# Shruthi-Analog-SVF-v02.net
KiCad netlist of a schematic drawn in EAGLE
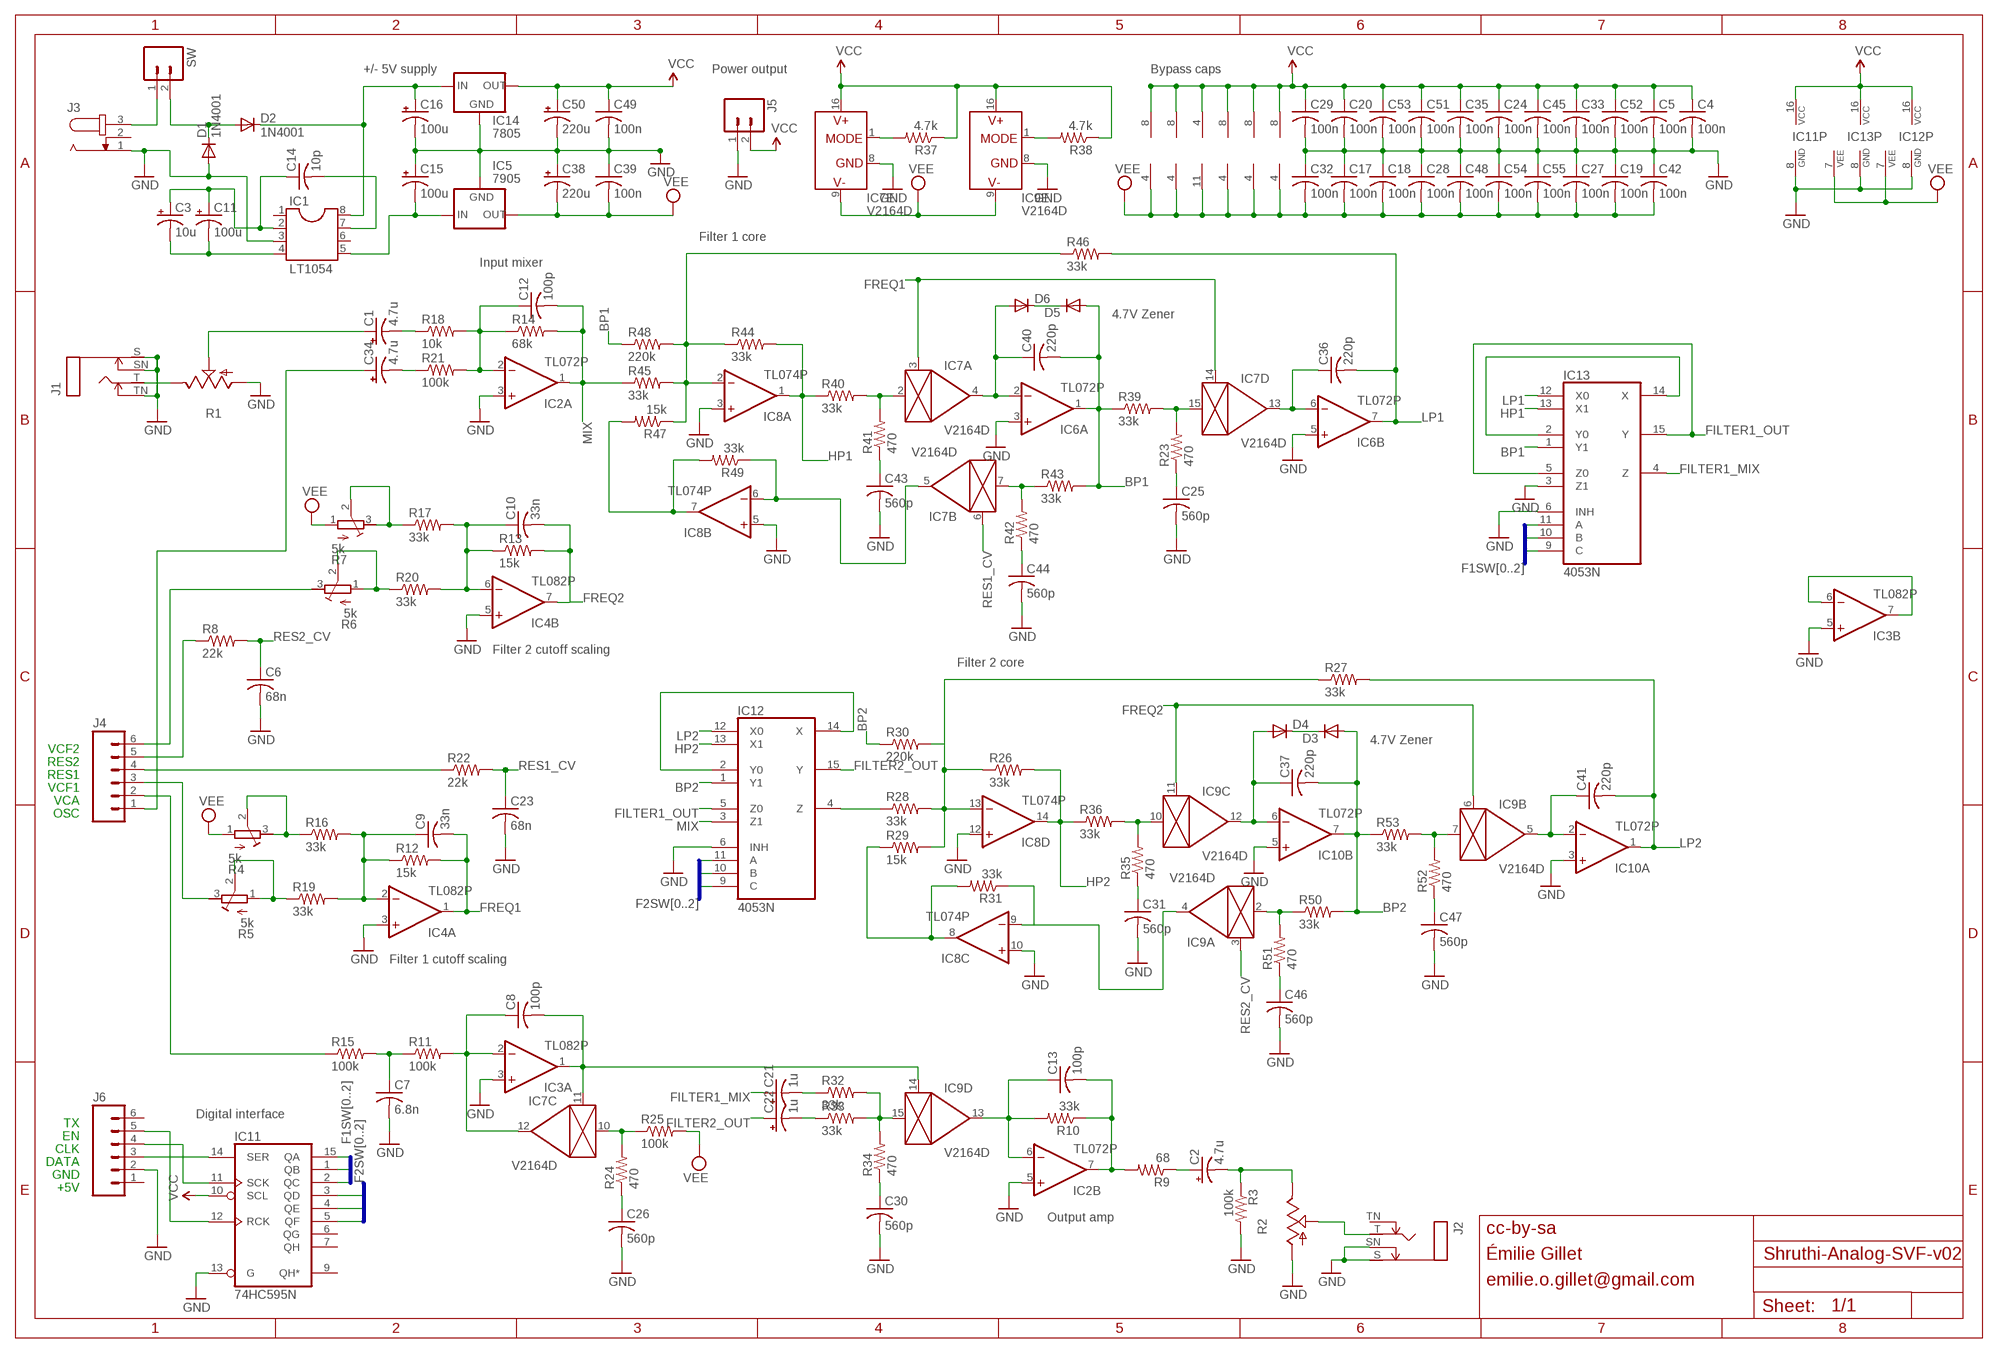
[diagram p0: schematic, sheet 1]

(export (version "E")
  (design (tool "Eeschema 10.0.6"))
  (components
    (comp (ref "C1")
      (value "4.7u")
      (footprint "eagle-import:E2,5-6")
      (libsource (lib "eagle-import") (part "CPOL-USE2.5-6"))
    )
    (comp (ref "C2")
      (value "4.7u")
      (footprint "eagle-import:E2,5-6")
      (libsource (lib "eagle-import") (part "CPOL-USE2.5-6"))
    )
    (comp (ref "C3")
      (value "10u")
      (footprint "eagle-import:E2,5-5")
      (libsource (lib "eagle-import") (part "CPOL-USE2.5-5"))
    )
    (comp (ref "C4")
      (value "100n")
      (footprint "eagle-import:C025-025X050")
      (libsource (lib "eagle-import") (part "C-US025-025X050"))
    )
    (comp (ref "C5")
      (value "100n")
      (footprint "eagle-import:C025-025X050")
      (libsource (lib "eagle-import") (part "C-US025-025X050"))
    )
    (comp (ref "C6")
      (value "68n")
      (footprint "eagle-import:C050-025X075")
      (libsource (lib "eagle-import") (part "C-US050-025X075"))
    )
    (comp (ref "C7")
      (value "6.8n")
      (footprint "eagle-import:C025-025X050")
      (libsource (lib "eagle-import") (part "C-US025-025X050"))
    )
    (comp (ref "C8")
      (value "100p")
      (footprint "eagle-import:C025-025X050")
      (libsource (lib "eagle-import") (part "C-US025-025X050"))
    )
    (comp (ref "C9")
      (value "33n")
      (footprint "eagle-import:C050-025X075")
      (libsource (lib "eagle-import") (part "C-US050-025X075"))
    )
    (comp (ref "C10")
      (value "33n")
      (footprint "eagle-import:C050-025X075")
      (libsource (lib "eagle-import") (part "C-US050-025X075"))
    )
    (comp (ref "C11")
      (value "100u")
      (footprint "eagle-import:E2,5-6")
      (libsource (lib "eagle-import") (part "CPOL-USE2.5-6"))
    )
    (comp (ref "C12")
      (value "100p")
      (footprint "eagle-import:C025-025X050")
      (libsource (lib "eagle-import") (part "C-US025-025X050"))
    )
    (comp (ref "C13")
      (value "100p")
      (footprint "eagle-import:C025-025X050")
      (libsource (lib "eagle-import") (part "C-US025-025X050"))
    )
    (comp (ref "C14")
      (value "10p")
      (footprint "eagle-import:C025-025X050")
      (libsource (lib "eagle-import") (part "C-US025-025X050"))
    )
    (comp (ref "C15")
      (value "100u")
      (footprint "eagle-import:E2,5-7")
      (libsource (lib "eagle-import") (part "CPOL-USE2.5-7"))
    )
    (comp (ref "C16")
      (value "100u")
      (footprint "eagle-import:E2,5-7")
      (libsource (lib "eagle-import") (part "CPOL-USE2.5-7"))
    )
    (comp (ref "C17")
      (value "100n")
      (footprint "eagle-import:C025-025X050")
      (libsource (lib "eagle-import") (part "C-US025-025X050"))
    )
    (comp (ref "C18")
      (value "100n")
      (footprint "eagle-import:C025-025X050")
      (libsource (lib "eagle-import") (part "C-US025-025X050"))
    )
    (comp (ref "C19")
      (value "100n")
      (footprint "eagle-import:C025-025X050")
      (libsource (lib "eagle-import") (part "C-US025-025X050"))
    )
    (comp (ref "C20")
      (value "100n")
      (footprint "eagle-import:C025-025X050")
      (libsource (lib "eagle-import") (part "C-US025-025X050"))
    )
    (comp (ref "C21")
      (value "1u")
      (footprint "eagle-import:E2,5-5")
      (libsource (lib "eagle-import") (part "CPOL-USE2.5-5"))
    )
    (comp (ref "C22")
      (value "1u")
      (footprint "eagle-import:E2,5-5")
      (libsource (lib "eagle-import") (part "CPOL-USE2.5-5"))
    )
    (comp (ref "C23")
      (value "68n")
      (footprint "eagle-import:C050-025X075")
      (libsource (lib "eagle-import") (part "C-US050-025X075"))
    )
    (comp (ref "C24")
      (value "100n")
      (footprint "eagle-import:C025-025X050")
      (libsource (lib "eagle-import") (part "C-US025-025X050"))
    )
    (comp (ref "C25")
      (value "560p")
      (footprint "eagle-import:C025-025X050")
      (libsource (lib "eagle-import") (part "C-US025-025X050"))
    )
    (comp (ref "C26")
      (value "560p")
      (footprint "eagle-import:C025-025X050")
      (libsource (lib "eagle-import") (part "C-US025-025X050"))
    )
    (comp (ref "C27")
      (value "100n")
      (footprint "eagle-import:C025-025X050")
      (libsource (lib "eagle-import") (part "C-US025-025X050"))
    )
    (comp (ref "C28")
      (value "100n")
      (footprint "eagle-import:C025-025X050")
      (libsource (lib "eagle-import") (part "C-US025-025X050"))
    )
    (comp (ref "C29")
      (value "100n")
      (footprint "eagle-import:C025-025X050")
      (libsource (lib "eagle-import") (part "C-US025-025X050"))
    )
    (comp (ref "C30")
      (value "560p")
      (footprint "eagle-import:C025-025X050")
      (libsource (lib "eagle-import") (part "C-US025-025X050"))
    )
    (comp (ref "C31")
      (value "560p")
      (footprint "eagle-import:C025-025X050")
      (libsource (lib "eagle-import") (part "C-US025-025X050"))
    )
    (comp (ref "C32")
      (value "100n")
      (footprint "eagle-import:C025-025X050")
      (libsource (lib "eagle-import") (part "C-US025-025X050"))
    )
    (comp (ref "C33")
      (value "100n")
      (footprint "eagle-import:C025-025X050")
      (libsource (lib "eagle-import") (part "C-US025-025X050"))
    )
    (comp (ref "C34")
      (value "4.7u")
      (footprint "eagle-import:E2,5-6")
      (libsource (lib "eagle-import") (part "CPOL-USE2.5-6"))
    )
    (comp (ref "C35")
      (value "100n")
      (footprint "eagle-import:C025-025X050")
      (libsource (lib "eagle-import") (part "C-US025-025X050"))
    )
    (comp (ref "C36")
      (value "220p")
      (footprint "eagle-import:C025-025X050")
      (libsource (lib "eagle-import") (part "C-US025-025X050"))
    )
    (comp (ref "C37")
      (value "220p")
      (footprint "eagle-import:C025-025X050")
      (libsource (lib "eagle-import") (part "C-US025-025X050"))
    )
    (comp (ref "C38")
      (value "220u")
      (footprint "eagle-import:E5-10,5")
      (libsource (lib "eagle-import") (part "CPOL-USE5-10.5"))
    )
    (comp (ref "C39")
      (value "100n")
      (footprint "eagle-import:C025-025X050")
      (libsource (lib "eagle-import") (part "C-US025-025X050"))
    )
    (comp (ref "C40")
      (value "220p")
      (footprint "eagle-import:C025-025X050")
      (libsource (lib "eagle-import") (part "C-US025-025X050"))
    )
    (comp (ref "C41")
      (value "220p")
      (footprint "eagle-import:C025-025X050")
      (libsource (lib "eagle-import") (part "C-US025-025X050"))
    )
    (comp (ref "C42")
      (value "100n")
      (footprint "eagle-import:C025-025X050")
      (libsource (lib "eagle-import") (part "C-US025-025X050"))
    )
    (comp (ref "C43")
      (value "560p")
      (footprint "eagle-import:C025-025X050")
      (libsource (lib "eagle-import") (part "C-US025-025X050"))
    )
    (comp (ref "C44")
      (value "560p")
      (footprint "eagle-import:C025-025X050")
      (libsource (lib "eagle-import") (part "C-US025-025X050"))
    )
    (comp (ref "C45")
      (value "100n")
      (footprint "eagle-import:C025-025X050")
      (libsource (lib "eagle-import") (part "C-US025-025X050"))
    )
    (comp (ref "C46")
      (value "560p")
      (footprint "eagle-import:C025-025X050")
      (libsource (lib "eagle-import") (part "C-US025-025X050"))
    )
    (comp (ref "C47")
      (value "560p")
      (footprint "eagle-import:C025-025X050")
      (libsource (lib "eagle-import") (part "C-US025-025X050"))
    )
    (comp (ref "C48")
      (value "100n")
      (footprint "eagle-import:C025-025X050")
      (libsource (lib "eagle-import") (part "C-US025-025X050"))
    )
    (comp (ref "C49")
      (value "100n")
      (footprint "eagle-import:C025-025X050")
      (libsource (lib "eagle-import") (part "C-US025-025X050"))
    )
    (comp (ref "C50")
      (value "220u")
      (footprint "eagle-import:E5-10,5")
      (libsource (lib "eagle-import") (part "CPOL-USE5-10.5"))
    )
    (comp (ref "C51")
      (value "100n")
      (footprint "eagle-import:C025-025X050")
      (libsource (lib "eagle-import") (part "C-US025-025X050"))
    )
    (comp (ref "C52")
      (value "100n")
      (footprint "eagle-import:C025-025X050")
      (libsource (lib "eagle-import") (part "C-US025-025X050"))
    )
    (comp (ref "C53")
      (value "100n")
      (footprint "eagle-import:C025-025X050")
      (libsource (lib "eagle-import") (part "C-US025-025X050"))
    )
    (comp (ref "C54")
      (value "100n")
      (footprint "eagle-import:C025-025X050")
      (libsource (lib "eagle-import") (part "C-US025-025X050"))
    )
    (comp (ref "C55")
      (value "100n")
      (footprint "eagle-import:C025-025X050")
      (libsource (lib "eagle-import") (part "C-US025-025X050"))
    )
    (comp (ref "D1")
      (value "1N4001")
      (footprint "eagle-import:DO41-10")
      (libsource (lib "eagle-import") (part "1N4004"))
    )
    (comp (ref "D2")
      (value "1N4001")
      (footprint "eagle-import:DO41-10")
      (libsource (lib "eagle-import") (part "1N4004"))
    )
    (comp (ref "D3")
      (value "DIODE-D-5")
      (footprint "eagle-import:D-5")
      (libsource (lib "eagle-import") (part "DIODE-D-5"))
    )
    (comp (ref "D4")
      (value "DIODE-D-5")
      (footprint "eagle-import:D-5")
      (libsource (lib "eagle-import") (part "DIODE-D-5"))
    )
    (comp (ref "D5")
      (value "DIODE-D-5")
      (footprint "eagle-import:D-5")
      (libsource (lib "eagle-import") (part "DIODE-D-5"))
    )
    (comp (ref "D6")
      (value "DIODE-D-5")
      (footprint "eagle-import:D-5")
      (libsource (lib "eagle-import") (part "DIODE-D-5"))
    )
    (comp (ref "IC1")
      (value "LT1054")
      (footprint "eagle-import:DIL08")
      (libsource (lib "eagle-import") (part "DIL8"))
    )
    (comp (ref "IC2")
      (value "TL072P")
      (footprint "eagle-import:DIL08")
      (libsource (lib "eagle-import") (part "TL072P"))
    )
    (comp (ref "IC3")
      (value "TL082P")
      (footprint "eagle-import:DIL08")
      (libsource (lib "eagle-import") (part "TL072P"))
    )
    (comp (ref "IC4")
      (value "TL082P")
      (footprint "eagle-import:DIL08")
      (libsource (lib "eagle-import") (part "TL072P"))
    )
    (comp (ref "IC5")
      (value "7905")
      (footprint "eagle-import:79XXS")
      (libsource (lib "eagle-import") (part "79XXS"))
    )
    (comp (ref "IC6")
      (value "TL072P")
      (footprint "eagle-import:DIL08")
      (libsource (lib "eagle-import") (part "TL072P"))
    )
    (comp (ref "IC7")
      (value "V2164D")
      (footprint "eagle-import:DIL16")
      (libsource (lib "eagle-import") (part "SSM2164P"))
    )
    (comp (ref "IC8")
      (value "TL074P")
      (footprint "eagle-import:DIL14")
      (libsource (lib "eagle-import") (part "TL074P"))
    )
    (comp (ref "IC9")
      (value "V2164D")
      (footprint "eagle-import:DIL16")
      (libsource (lib "eagle-import") (part "SSM2164P"))
    )
    (comp (ref "IC10")
      (value "TL072P")
      (footprint "eagle-import:DIL08")
      (libsource (lib "eagle-import") (part "TL072P"))
    )
    (comp (ref "IC11")
      (value "74HC595N")
      (footprint "eagle-import:DIL16")
      (libsource (lib "eagle-import") (part "74595NHC"))
    )
    (comp (ref "IC12")
      (value "4053N")
      (footprint "eagle-import:DIL16")
      (libsource (lib "eagle-import") (part "4053N"))
    )
    (comp (ref "IC13")
      (value "4053N")
      (footprint "eagle-import:DIL16")
      (libsource (lib "eagle-import") (part "4053N"))
    )
    (comp (ref "IC14")
      (value "7805")
      (footprint "eagle-import:78XXS")
      (libsource (lib "eagle-import") (part "78XXS"))
    )
    (comp (ref "J1")
      (value "MONOSWS")
      (footprint "eagle-import:NMJ4HC-S")
      (libsource (lib "eagle-import") (part "MONOSWS"))
    )
    (comp (ref "J2")
      (value "MONOSWS")
      (footprint "eagle-import:NMJ4HC-S")
      (libsource (lib "eagle-import") (part "MONOSWS"))
    )
    (comp (ref "J3")
      (value "JACK-PLUG1")
      (footprint "eagle-import:SPC4078")
      (libsource (lib "eagle-import") (part "JACK-PLUG1"))
    )
    (comp (ref "J4")
      (value "M06SIP")
      (footprint "eagle-import:1X06")
      (libsource (lib "eagle-import") (part "M06SIP"))
    )
    (comp (ref "J5")
      (value "M02PTH")
      (footprint "eagle-import:1X02")
      (libsource (lib "eagle-import") (part "M02PTH"))
    )
    (comp (ref "J6")
      (value "M06SIP")
      (footprint "eagle-import:1X06")
      (libsource (lib "eagle-import") (part "M06SIP"))
    )
    (comp (ref "R1")
      (value "POT_USCABLED")
      (footprint "eagle-import:CABLE_POT_6MM")
      (libsource (lib "eagle-import") (part "POT_USCABLED"))
    )
    (comp (ref "R2")
      (value "POT_USCABLED")
      (footprint "eagle-import:CABLE_POT_6MM")
      (libsource (lib "eagle-import") (part "POT_USCABLED"))
    )
    (comp (ref "R3")
      (value "100k")
      (footprint "eagle-import:0204_7")
      (libsource (lib "eagle-import") (part "R-US_0204/7"))
    )
    (comp (ref "R4")
      (value "5k")
      (footprint "eagle-import:RTRIM3296W")
      (libsource (lib "eagle-import") (part "R-TRIMM3296W"))
    )
    (comp (ref "R5")
      (value "5k")
      (footprint "eagle-import:RTRIM3296W")
      (libsource (lib "eagle-import") (part "R-TRIMM3296W"))
    )
    (comp (ref "R6")
      (value "5k")
      (footprint "eagle-import:RTRIM3296W")
      (libsource (lib "eagle-import") (part "R-TRIMM3296W"))
    )
    (comp (ref "R7")
      (value "5k")
      (footprint "eagle-import:RTRIM3296W")
      (libsource (lib "eagle-import") (part "R-TRIMM3296W"))
    )
    (comp (ref "R8")
      (value "22k")
      (footprint "eagle-import:0204_7")
      (libsource (lib "eagle-import") (part "R-US_0204/7"))
    )
    (comp (ref "R9")
      (value "68")
      (footprint "eagle-import:0204_7")
      (libsource (lib "eagle-import") (part "R-US_0204/7"))
    )
    (comp (ref "R10")
      (value "33k")
      (footprint "eagle-import:0204_7")
      (libsource (lib "eagle-import") (part "R-US_0204/7"))
    )
    (comp (ref "R11")
      (value "100k")
      (footprint "eagle-import:0204_7")
      (libsource (lib "eagle-import") (part "R-US_0204/7"))
    )
    (comp (ref "R12")
      (value "15k")
      (footprint "eagle-import:0204_7")
      (libsource (lib "eagle-import") (part "R-US_0204/7"))
    )
    (comp (ref "R13")
      (value "15k")
      (footprint "eagle-import:0204_7")
      (libsource (lib "eagle-import") (part "R-US_0204/7"))
    )
    (comp (ref "R14")
      (value "68k")
      (footprint "eagle-import:0204_7")
      (libsource (lib "eagle-import") (part "R-US_0204/7"))
    )
    (comp (ref "R15")
      (value "100k")
      (footprint "eagle-import:0204_7")
      (libsource (lib "eagle-import") (part "R-US_0204/7"))
    )
    (comp (ref "R16")
      (value "33k")
      (footprint "eagle-import:0204_7")
      (libsource (lib "eagle-import") (part "R-US_0204/7"))
    )
    (comp (ref "R17")
      (value "33k")
      (footprint "eagle-import:0204_7")
      (libsource (lib "eagle-import") (part "R-US_0204/7"))
    )
    (comp (ref "R18")
      (value "10k")
      (footprint "eagle-import:0204_7")
      (libsource (lib "eagle-import") (part "R-US_0204/7"))
    )
    (comp (ref "R19")
      (value "33k")
      (footprint "eagle-import:0204_7")
      (libsource (lib "eagle-import") (part "R-US_0204/7"))
    )
    (comp (ref "R20")
      (value "33k")
      (footprint "eagle-import:0204_7")
      (libsource (lib "eagle-import") (part "R-US_0204/7"))
    )
    (comp (ref "R21")
      (value "100k")
      (footprint "eagle-import:0204_7")
      (libsource (lib "eagle-import") (part "R-US_0204/7"))
    )
    (comp (ref "R22")
      (value "22k")
      (footprint "eagle-import:0204_7")
      (libsource (lib "eagle-import") (part "R-US_0204/7"))
    )
    (comp (ref "R23")
      (value "470")
      (footprint "eagle-import:0204_7")
      (libsource (lib "eagle-import") (part "R-US_0204/7"))
    )
    (comp (ref "R24")
      (value "470")
      (footprint "eagle-import:0204_7")
      (libsource (lib "eagle-import") (part "R-US_0204/7"))
    )
    (comp (ref "R25")
      (value "100k")
      (footprint "eagle-import:0204_7")
      (libsource (lib "eagle-import") (part "R-US_0204/7"))
    )
    (comp (ref "R26")
      (value "33k")
      (footprint "eagle-import:0204_7")
      (libsource (lib "eagle-import") (part "R-US_0204/7"))
    )
    (comp (ref "R27")
      (value "33k")
      (footprint "eagle-import:0204_7")
      (libsource (lib "eagle-import") (part "R-US_0204/7"))
    )
    (comp (ref "R28")
      (value "33k")
      (footprint "eagle-import:0204_7")
      (libsource (lib "eagle-import") (part "R-US_0204/7"))
    )
    (comp (ref "R29")
      (value "15k")
      (footprint "eagle-import:0204_7")
      (libsource (lib "eagle-import") (part "R-US_0204/7"))
    )
    (comp (ref "R30")
      (value "220k")
      (footprint "eagle-import:0204_7")
      (libsource (lib "eagle-import") (part "R-US_0204/7"))
    )
    (comp (ref "R31")
      (value "33k")
      (footprint "eagle-import:0204_7")
      (libsource (lib "eagle-import") (part "R-US_0204/7"))
    )
    (comp (ref "R32")
      (value "33k")
      (footprint "eagle-import:0204_7")
      (libsource (lib "eagle-import") (part "R-US_0204/7"))
    )
    (comp (ref "R33")
      (value "33k")
      (footprint "eagle-import:0204_7")
      (libsource (lib "eagle-import") (part "R-US_0204/7"))
    )
    (comp (ref "R34")
      (value "470")
      (footprint "eagle-import:0204_7")
      (libsource (lib "eagle-import") (part "R-US_0204/7"))
    )
    (comp (ref "R35")
      (value "470")
      (footprint "eagle-import:0204_7")
      (libsource (lib "eagle-import") (part "R-US_0204/7"))
    )
    (comp (ref "R36")
      (value "33k")
      (footprint "eagle-import:0204_7")
      (libsource (lib "eagle-import") (part "R-US_0204/7"))
    )
    (comp (ref "R37")
      (value "4.7k")
      (footprint "eagle-import:0204_7")
      (libsource (lib "eagle-import") (part "R-US_0204/7"))
    )
    (comp (ref "R38")
      (value "4.7k")
      (footprint "eagle-import:0204_7")
      (libsource (lib "eagle-import") (part "R-US_0204/7"))
    )
    (comp (ref "R39")
      (value "33k")
      (footprint "eagle-import:0204_7")
      (libsource (lib "eagle-import") (part "R-US_0204/7"))
    )
    (comp (ref "R40")
      (value "33k")
      (footprint "eagle-import:0204_7")
      (libsource (lib "eagle-import") (part "R-US_0204/7"))
    )
    (comp (ref "R41")
      (value "470")
      (footprint "eagle-import:0204_7")
      (libsource (lib "eagle-import") (part "R-US_0204/7"))
    )
    (comp (ref "R42")
      (value "470")
      (footprint "eagle-import:0204_7")
      (libsource (lib "eagle-import") (part "R-US_0204/7"))
    )
    (comp (ref "R43")
      (value "33k")
      (footprint "eagle-import:0204_7")
      (libsource (lib "eagle-import") (part "R-US_0204/7"))
    )
    (comp (ref "R44")
      (value "33k")
      (footprint "eagle-import:0204_7")
      (libsource (lib "eagle-import") (part "R-US_0204/7"))
    )
    (comp (ref "R45")
      (value "33k")
      (footprint "eagle-import:0204_7")
      (libsource (lib "eagle-import") (part "R-US_0204/7"))
    )
    (comp (ref "R46")
      (value "33k")
      (footprint "eagle-import:0204_7")
      (libsource (lib "eagle-import") (part "R-US_0204/7"))
    )
    (comp (ref "R47")
      (value "15k")
      (footprint "eagle-import:0204_7")
      (libsource (lib "eagle-import") (part "R-US_0204/7"))
    )
    (comp (ref "R48")
      (value "220k")
      (footprint "eagle-import:0204_7")
      (libsource (lib "eagle-import") (part "R-US_0204/7"))
    )
    (comp (ref "R49")
      (value "33k")
      (footprint "eagle-import:0204_7")
      (libsource (lib "eagle-import") (part "R-US_0204/7"))
    )
    (comp (ref "R50")
      (value "33k")
      (footprint "eagle-import:0204_7")
      (libsource (lib "eagle-import") (part "R-US_0204/7"))
    )
    (comp (ref "R51")
      (value "470")
      (footprint "eagle-import:0204_7")
      (libsource (lib "eagle-import") (part "R-US_0204/7"))
    )
    (comp (ref "R52")
      (value "470")
      (footprint "eagle-import:0204_7")
      (libsource (lib "eagle-import") (part "R-US_0204/7"))
    )
    (comp (ref "R53")
      (value "33k")
      (footprint "eagle-import:0204_7")
      (libsource (lib "eagle-import") (part "R-US_0204/7"))
    )
    (comp (ref "SW")
      (value "M02PTH")
      (footprint "eagle-import:1X02")
      (libsource (lib "eagle-import") (part "M02PTH"))
    )
  )
  (nets
    (net (code "1") (name "/BP1") (class "Default")
      (node (ref "C40") (pin "2") (pinfunction "2_2") (pintype "passive"))
      (node (ref "D5") (pin "A") (pinfunction "A_A") (pintype "passive"))
      (node (ref "IC13") (pin "1") (pinfunction "Y1_1") (pintype "bidirectional"))
      (node (ref "IC6") (pin "1") (pinfunction "OUT_1") (pintype "output"))
      (node (ref "R39") (pin "1") (pinfunction "1_1") (pintype "passive"))
      (node (ref "R43") (pin "2") (pinfunction "2_2") (pintype "passive"))
      (node (ref "R48") (pin "1") (pinfunction "1_1") (pintype "passive"))
    )
    (net (code "2") (name "/BP2") (class "Default")
      (node (ref "C37") (pin "2") (pinfunction "2_2") (pintype "passive"))
      (node (ref "D3") (pin "A") (pinfunction "A_A") (pintype "passive"))
      (node (ref "IC10") (pin "7") (pinfunction "OUT_7") (pintype "output"))
      (node (ref "IC12") (pin "1") (pinfunction "Y1_1") (pintype "bidirectional"))
      (node (ref "R30") (pin "1") (pinfunction "1_1") (pintype "passive"))
      (node (ref "R50") (pin "2") (pinfunction "2_2") (pintype "passive"))
      (node (ref "R53") (pin "1") (pinfunction "1_1") (pintype "passive"))
    )
    (net (code "3") (name "/F1SW0") (class "Default")
      (node (ref "IC11") (pin "15") (pinfunction "QA_15") (pintype "tri_state"))
      (node (ref "IC13") (pin "9") (pinfunction "C_9") (pintype "input"))
    )
    (net (code "4") (name "/F1SW1") (class "Default")
      (node (ref "IC11") (pin "1") (pinfunction "QB_1") (pintype "tri_state"))
      (node (ref "IC13") (pin "10") (pinfunction "B_10") (pintype "input"))
    )
    (net (code "5") (name "/F1SW2") (class "Default")
      (node (ref "IC11") (pin "2") (pinfunction "QC_2") (pintype "tri_state"))
      (node (ref "IC13") (pin "11") (pinfunction "A_11") (pintype "input"))
    )
    (net (code "7") (name "/F2SW0") (class "Default")
      (node (ref "IC11") (pin "3") (pinfunction "QD_3") (pintype "tri_state"))
      (node (ref "IC12") (pin "9") (pinfunction "C_9") (pintype "input"))
    )
    (net (code "8") (name "/F2SW1") (class "Default")
      (node (ref "IC11") (pin "4") (pinfunction "QE_4") (pintype "tri_state"))
      (node (ref "IC12") (pin "10") (pinfunction "B_10") (pintype "input"))
    )
    (net (code "9") (name "/F2SW2") (class "Default")
      (node (ref "IC11") (pin "5") (pinfunction "QF_5") (pintype "tri_state"))
      (node (ref "IC12") (pin "11") (pinfunction "A_11") (pintype "input"))
    )
    (net (code "11") (name "/FILTER1_MIX") (class "Default")
      (node (ref "C21") (pin "+") (pinfunction "+_+") (pintype "passive"))
      (node (ref "IC13") (pin "4") (pinfunction "Z_4") (pintype "bidirectional"))
    )
    (net (code "12") (name "/FILTER1_OUT") (class "Default")
      (node (ref "IC12") (pin "5") (pinfunction "Z0_5") (pintype "bidirectional"))
      (node (ref "IC13") (pin "15") (pinfunction "Y_15") (pintype "bidirectional"))
      (node (ref "IC13") (pin "5") (pinfunction "Z0_5") (pintype "bidirectional"))
    )
    (net (code "13") (name "/FILTER2_OUT") (class "Default")
      (node (ref "C22") (pin "+") (pinfunction "+_+") (pintype "passive"))
      (node (ref "IC12") (pin "15") (pinfunction "Y_15") (pintype "bidirectional"))
    )
    (net (code "14") (name "/FREQ1") (class "Default")
      (node (ref "C9") (pin "2") (pinfunction "2_2") (pintype "passive"))
      (node (ref "IC4") (pin "1") (pinfunction "OUT_1") (pintype "output"))
      (node (ref "IC7") (pin "14") (pinfunction "CTRL_14") (pintype "input"))
      (node (ref "IC7") (pin "3") (pinfunction "CTRL_3") (pintype "input"))
      (node (ref "R12") (pin "2") (pinfunction "2_2") (pintype "passive"))
    )
    (net (code "15") (name "/FREQ2") (class "Default")
      (node (ref "C10") (pin "2") (pinfunction "2_2") (pintype "passive"))
      (node (ref "IC4") (pin "7") (pinfunction "OUT_7") (pintype "output"))
      (node (ref "IC9") (pin "11") (pinfunction "CTRL_11") (pintype "input"))
      (node (ref "IC9") (pin "6") (pinfunction "CTRL_6") (pintype "input"))
      (node (ref "R13") (pin "2") (pinfunction "2_2") (pintype "passive"))
    )
    (net (code "16") (name "/HP1") (class "Default")
      (node (ref "IC13") (pin "13") (pinfunction "X1_13") (pintype "bidirectional"))
      (node (ref "IC8") (pin "1") (pinfunction "OUT_1") (pintype "output"))
      (node (ref "R40") (pin "1") (pinfunction "1_1") (pintype "passive"))
      (node (ref "R44") (pin "2") (pinfunction "2_2") (pintype "passive"))
    )
    (net (code "17") (name "/HP2") (class "Default")
      (node (ref "IC12") (pin "13") (pinfunction "X1_13") (pintype "bidirectional"))
      (node (ref "IC8") (pin "14") (pinfunction "OUT_14") (pintype "output"))
      (node (ref "R26") (pin "2") (pinfunction "2_2") (pintype "passive"))
      (node (ref "R36") (pin "1") (pinfunction "1_1") (pintype "passive"))
    )
    (net (code "18") (name "/LP1") (class "Default")
      (node (ref "C36") (pin "2") (pinfunction "2_2") (pintype "passive"))
      (node (ref "IC13") (pin "12") (pinfunction "X0_12") (pintype "bidirectional"))
      (node (ref "IC6") (pin "7") (pinfunction "OUT_7") (pintype "output"))
      (node (ref "R46") (pin "2") (pinfunction "2_2") (pintype "passive"))
    )
    (net (code "19") (name "/LP2") (class "Default")
      (node (ref "C41") (pin "2") (pinfunction "2_2") (pintype "passive"))
      (node (ref "IC10") (pin "1") (pinfunction "OUT_1") (pintype "output"))
      (node (ref "IC12") (pin "12") (pinfunction "X0_12") (pintype "bidirectional"))
      (node (ref "R27") (pin "2") (pinfunction "2_2") (pintype "passive"))
    )
    (net (code "20") (name "/MIX") (class "Default")
      (node (ref "C12") (pin "2") (pinfunction "2_2") (pintype "passive"))
      (node (ref "IC12") (pin "3") (pinfunction "Z1_3") (pintype "bidirectional"))
      (node (ref "IC2") (pin "1") (pinfunction "OUT_1") (pintype "output"))
      (node (ref "R14") (pin "2") (pinfunction "2_2") (pintype "passive"))
      (node (ref "R45") (pin "1") (pinfunction "1_1") (pintype "passive"))
    )
    (net (code "21") (name "/RES1_CV") (class "Default")
      (node (ref "C23") (pin "1") (pinfunction "1_1") (pintype "passive"))
      (node (ref "IC7") (pin "6") (pinfunction "CTRL_6") (pintype "input"))
      (node (ref "R22") (pin "2") (pinfunction "2_2") (pintype "passive"))
    )
    (net (code "22") (name "/RES2_CV") (class "Default")
      (node (ref "C6") (pin "1") (pinfunction "1_1") (pintype "passive"))
      (node (ref "IC9") (pin "3") (pinfunction "CTRL_3") (pintype "input"))
      (node (ref "R8") (pin "2") (pinfunction "2_2") (pintype "passive"))
    )
    (net (code "23") (name "GND") (class "Default")
      (node (ref "C15") (pin "+") (pinfunction "+_+") (pintype "passive"))
      (node (ref "C16") (pin "-") (pinfunction "-_-") (pintype "passive"))
      (node (ref "C17") (pin "1") (pinfunction "1_1") (pintype "passive"))
      (node (ref "C18") (pin "1") (pinfunction "1_1") (pintype "passive"))
      (node (ref "C19") (pin "1") (pinfunction "1_1") (pintype "passive"))
      (node (ref "C20") (pin "2") (pinfunction "2_2") (pintype "passive"))
      (node (ref "C23") (pin "2") (pinfunction "2_2") (pintype "passive"))
      (node (ref "C24") (pin "2") (pinfunction "2_2") (pintype "passive"))
      (node (ref "C25") (pin "2") (pinfunction "2_2") (pintype "passive"))
      (node (ref "C26") (pin "2") (pinfunction "2_2") (pintype "passive"))
      (node (ref "C27") (pin "1") (pinfunction "1_1") (pintype "passive"))
      (node (ref "C28") (pin "1") (pinfunction "1_1") (pintype "passive"))
      (node (ref "C29") (pin "2") (pinfunction "2_2") (pintype "passive"))
      (node (ref "C30") (pin "2") (pinfunction "2_2") (pintype "passive"))
      (node (ref "C31") (pin "2") (pinfunction "2_2") (pintype "passive"))
      (node (ref "C32") (pin "1") (pinfunction "1_1") (pintype "passive"))
      (node (ref "C33") (pin "2") (pinfunction "2_2") (pintype "passive"))
      (node (ref "C35") (pin "2") (pinfunction "2_2") (pintype "passive"))
      (node (ref "C38") (pin "+") (pinfunction "+_+") (pintype "passive"))
      (node (ref "C39") (pin "1") (pinfunction "1_1") (pintype "passive"))
      (node (ref "C4") (pin "2") (pinfunction "2_2") (pintype "passive"))
      (node (ref "C42") (pin "1") (pinfunction "1_1") (pintype "passive"))
      (node (ref "C43") (pin "2") (pinfunction "2_2") (pintype "passive"))
      (node (ref "C44") (pin "2") (pinfunction "2_2") (pintype "passive"))
      (node (ref "C45") (pin "2") (pinfunction "2_2") (pintype "passive"))
      (node (ref "C46") (pin "2") (pinfunction "2_2") (pintype "passive"))
      (node (ref "C47") (pin "2") (pinfunction "2_2") (pintype "passive"))
      (node (ref "C48") (pin "1") (pinfunction "1_1") (pintype "passive"))
      (node (ref "C49") (pin "2") (pinfunction "2_2") (pintype "passive"))
      (node (ref "C5") (pin "2") (pinfunction "2_2") (pintype "passive"))
      (node (ref "C50") (pin "-") (pinfunction "-_-") (pintype "passive"))
      (node (ref "C51") (pin "2") (pinfunction "2_2") (pintype "passive"))
      (node (ref "C52") (pin "2") (pinfunction "2_2") (pintype "passive"))
      (node (ref "C53") (pin "2") (pinfunction "2_2") (pintype "passive"))
      (node (ref "C54") (pin "1") (pinfunction "1_1") (pintype "passive"))
      (node (ref "C55") (pin "1") (pinfunction "1_1") (pintype "passive"))
      (node (ref "C6") (pin "2") (pinfunction "2_2") (pintype "passive"))
      (node (ref "C7") (pin "2") (pinfunction "2_2") (pintype "passive"))
      (node (ref "D1") (pin "A") (pinfunction "A_A") (pintype "passive"))
      (node (ref "IC1") (pin "3") (pinfunction "3_3") (pintype "passive"))
      (node (ref "IC10") (pin "3") (pinfunction "+IN_3") (pintype "input"))
      (node (ref "IC10") (pin "5") (pinfunction "+IN_5") (pintype "input"))
      (node (ref "IC11") (pin "13") (pinfunction "G_13") (pintype "input"))
      (node (ref "IC11") (pin "8") (pinfunction "GND_8") (pintype "power_in"))
      (node (ref "IC12") (pin "6") (pinfunction "INH_6") (pintype "input"))
      (node (ref "IC12") (pin "8") (pinfunction "GND_8") (pintype "power_in"))
      (node (ref "IC13") (pin "3") (pinfunction "Z1_3") (pintype "bidirectional"))
      (node (ref "IC13") (pin "6") (pinfunction "INH_6") (pintype "input"))
      (node (ref "IC13") (pin "8") (pinfunction "GND_8") (pintype "power_in"))
      (node (ref "IC14") (pin "GND") (pinfunction "GND_GND") (pintype "input"))
      (node (ref "IC2") (pin "3") (pinfunction "+IN_3") (pintype "input"))
      (node (ref "IC2") (pin "5") (pinfunction "+IN_5") (pintype "input"))
      (node (ref "IC3") (pin "3") (pinfunction "+IN_3") (pintype "input"))
      (node (ref "IC3") (pin "5") (pinfunction "+IN_5") (pintype "input"))
      (node (ref "IC4") (pin "3") (pinfunction "+IN_3") (pintype "input"))
      (node (ref "IC4") (pin "5") (pinfunction "+IN_5") (pintype "input"))
      (node (ref "IC5") (pin "GND") (pinfunction "GND_GND") (pintype "input"))
      (node (ref "IC6") (pin "3") (pinfunction "+IN_3") (pintype "input"))
      (node (ref "IC6") (pin "5") (pinfunction "+IN_5") (pintype "input"))
      (node (ref "IC7") (pin "8") (pinfunction "GND_8") (pintype "power_in"))
      (node (ref "IC8") (pin "10") (pinfunction "+IN_10") (pintype "input"))
      (node (ref "IC8") (pin "12") (pinfunction "+IN_12") (pintype "input"))
      (node (ref "IC8") (pin "3") (pinfunction "+IN_3") (pintype "input"))
      (node (ref "IC8") (pin "5") (pinfunction "+IN_5") (pintype "input"))
      (node (ref "IC9") (pin "8") (pinfunction "GND_8") (pintype "power_in"))
      (node (ref "J1") (pin "S") (pinfunction "S_S") (pintype "passive"))
      (node (ref "J1") (pin "SN") (pinfunction "SN_SN") (pintype "passive"))
      (node (ref "J1") (pin "TN") (pinfunction "TN_TN") (pintype "passive"))
      (node (ref "J2") (pin "S") (pinfunction "S_S") (pintype "passive"))
      (node (ref "J2") (pin "SN") (pinfunction "SN_SN") (pintype "passive"))
      (node (ref "J3") (pin "1") (pinfunction "1_1") (pintype "passive"))
      (node (ref "J5") (pin "1") (pinfunction "1_1") (pintype "passive"))
      (node (ref "J6") (pin "2") (pinfunction "2_2") (pintype "passive"))
      (node (ref "R1") (pin "A") (pinfunction "A_A") (pintype "passive"))
      (node (ref "R2") (pin "A") (pinfunction "A_A") (pintype "passive"))
      (node (ref "R3") (pin "2") (pinfunction "2_2") (pintype "passive"))
    )
    (net (code "24") (name "Net-(C1-Pad+)") (class "Default")
      (node (ref "C1") (pin "+") (pinfunction "+_+") (pintype "passive"))
      (node (ref "R1") (pin "S") (pinfunction "S_S") (pintype "passive"))
    )
    (net (code "25") (name "Net-(C1-Pad-)") (class "Default")
      (node (ref "C1") (pin "-") (pinfunction "-_-") (pintype "passive"))
      (node (ref "R18") (pin "1") (pinfunction "1_1") (pintype "passive"))
    )
    (net (code "26") (name "Net-(C2-Pad+)") (class "Default")
      (node (ref "C2") (pin "+") (pinfunction "+_+") (pintype "passive"))
      (node (ref "R9") (pin "1") (pinfunction "1_1") (pintype "passive"))
    )
    (net (code "27") (name "Net-(C2-Pad-)") (class "Default")
      (node (ref "C2") (pin "-") (pinfunction "-_-") (pintype "passive"))
      (node (ref "R2") (pin "E") (pinfunction "E_E") (pintype "passive"))
      (node (ref "R3") (pin "1") (pinfunction "1_1") (pintype "passive"))
    )
    (net (code "28") (name "Net-(C7-Pad1)") (class "Default")
      (node (ref "C7") (pin "1") (pinfunction "1_1") (pintype "passive"))
      (node (ref "R11") (pin "1") (pinfunction "1_1") (pintype "passive"))
      (node (ref "R15") (pin "2") (pinfunction "2_2") (pintype "passive"))
    )
    (net (code "29") (name "Net-(C11-Pad+)") (class "Default")
      (node (ref "C11") (pin "+") (pinfunction "+_+") (pintype "passive"))
      (node (ref "C14") (pin "1") (pinfunction "1_1") (pintype "passive"))
      (node (ref "C3") (pin "+") (pinfunction "+_+") (pintype "passive"))
      (node (ref "IC1") (pin "2") (pinfunction "2_2") (pintype "passive"))
    )
    (net (code "30") (name "Net-(C11-Pad-)") (class "Default")
      (node (ref "C11") (pin "-") (pinfunction "-_-") (pintype "passive"))
      (node (ref "C3") (pin "-") (pinfunction "-_-") (pintype "passive"))
      (node (ref "IC1") (pin "4") (pinfunction "4_4") (pintype "passive"))
    )
    (net (code "31") (name "Net-(C14-Pad2)") (class "Default")
      (node (ref "C14") (pin "2") (pinfunction "2_2") (pintype "passive"))
      (node (ref "IC1") (pin "7") (pinfunction "7_7") (pintype "passive"))
    )
    (net (code "32") (name "Net-(C15-Pad-)") (class "Default")
      (node (ref "C15") (pin "-") (pinfunction "-_-") (pintype "passive"))
      (node (ref "IC1") (pin "5") (pinfunction "5_5") (pintype "passive"))
      (node (ref "IC5") (pin "IN") (pinfunction "IN_IN") (pintype "input"))
    )
    (net (code "33") (name "Net-(C16-Pad+)") (class "Default")
      (node (ref "C16") (pin "+") (pinfunction "+_+") (pintype "passive"))
      (node (ref "D2") (pin "C") (pinfunction "C_C") (pintype "passive"))
      (node (ref "IC1") (pin "8") (pinfunction "8_8") (pintype "passive"))
      (node (ref "IC14") (pin "IN") (pinfunction "IN_IN") (pintype "input"))
    )
    (net (code "34") (name "Net-(C21-Pad-)") (class "Default")
      (node (ref "C21") (pin "-") (pinfunction "-_-") (pintype "passive"))
      (node (ref "R32") (pin "1") (pinfunction "1_1") (pintype "passive"))
    )
    (net (code "35") (name "Net-(C22-Pad-)") (class "Default")
      (node (ref "C22") (pin "-") (pinfunction "-_-") (pintype "passive"))
      (node (ref "R33") (pin "1") (pinfunction "1_1") (pintype "passive"))
    )
    (net (code "36") (name "Net-(C25-Pad1)") (class "Default")
      (node (ref "C25") (pin "1") (pinfunction "1_1") (pintype "passive"))
      (node (ref "R23") (pin "1") (pinfunction "1_1") (pintype "passive"))
    )
    (net (code "37") (name "Net-(C26-Pad1)") (class "Default")
      (node (ref "C26") (pin "1") (pinfunction "1_1") (pintype "passive"))
      (node (ref "R24") (pin "1") (pinfunction "1_1") (pintype "passive"))
    )
    (net (code "38") (name "Net-(C30-Pad1)") (class "Default")
      (node (ref "C30") (pin "1") (pinfunction "1_1") (pintype "passive"))
      (node (ref "R34") (pin "1") (pinfunction "1_1") (pintype "passive"))
    )
    (net (code "39") (name "Net-(C31-Pad1)") (class "Default")
      (node (ref "C31") (pin "1") (pinfunction "1_1") (pintype "passive"))
      (node (ref "R35") (pin "1") (pinfunction "1_1") (pintype "passive"))
    )
    (net (code "40") (name "Net-(C34-Pad+)") (class "Default")
      (node (ref "C34") (pin "+") (pinfunction "+_+") (pintype "passive"))
      (node (ref "J4") (pin "1") (pinfunction "1_1") (pintype "passive"))
    )
    (net (code "41") (name "Net-(C34-Pad-)") (class "Default")
      (node (ref "C34") (pin "-") (pinfunction "-_-") (pintype "passive"))
      (node (ref "R21") (pin "1") (pinfunction "1_1") (pintype "passive"))
    )
    (net (code "42") (name "Net-(C43-Pad1)") (class "Default")
      (node (ref "C43") (pin "1") (pinfunction "1_1") (pintype "passive"))
      (node (ref "R41") (pin "1") (pinfunction "1_1") (pintype "passive"))
    )
    (net (code "43") (name "Net-(C44-Pad1)") (class "Default")
      (node (ref "C44") (pin "1") (pinfunction "1_1") (pintype "passive"))
      (node (ref "R42") (pin "1") (pinfunction "1_1") (pintype "passive"))
    )
    (net (code "44") (name "Net-(C46-Pad1)") (class "Default")
      (node (ref "C46") (pin "1") (pinfunction "1_1") (pintype "passive"))
      (node (ref "R51") (pin "1") (pinfunction "1_1") (pintype "passive"))
    )
    (net (code "45") (name "Net-(C47-Pad1)") (class "Default")
      (node (ref "C47") (pin "1") (pinfunction "1_1") (pintype "passive"))
      (node (ref "R52") (pin "1") (pinfunction "1_1") (pintype "passive"))
    )
    (net (code "46") (name "Net-(D1-PadC)") (class "Default")
      (node (ref "D1") (pin "C") (pinfunction "C_C") (pintype "passive"))
      (node (ref "D2") (pin "A") (pinfunction "A_A") (pintype "passive"))
      (node (ref "SW") (pin "2") (pinfunction "2_2") (pintype "passive"))
    )
    (net (code "47") (name "Net-(D3-PadC)") (class "Default")
      (node (ref "D3") (pin "C") (pinfunction "C_C") (pintype "passive"))
      (node (ref "D4") (pin "C") (pinfunction "C_C") (pintype "passive"))
    )
    (net (code "48") (name "Net-(D5-PadC)") (class "Default")
      (node (ref "D5") (pin "C") (pinfunction "C_C") (pintype "passive"))
      (node (ref "D6") (pin "C") (pinfunction "C_C") (pintype "passive"))
    )
    (net (code "49") (name "Net-(IC2A--IN)") (class "Default")
      (node (ref "C12") (pin "1") (pinfunction "1_1") (pintype "passive"))
      (node (ref "IC2") (pin "2") (pinfunction "-IN_2") (pintype "input"))
      (node (ref "R14") (pin "1") (pinfunction "1_1") (pintype "passive"))
      (node (ref "R18") (pin "2") (pinfunction "2_2") (pintype "passive"))
      (node (ref "R21") (pin "2") (pinfunction "2_2") (pintype "passive"))
    )
    (net (code "50") (name "Net-(IC2B--IN)") (class "Default")
      (node (ref "C13") (pin "1") (pinfunction "1_1") (pintype "passive"))
      (node (ref "IC2") (pin "6") (pinfunction "-IN_6") (pintype "input"))
      (node (ref "IC9") (pin "13") (pinfunction "OUT_13") (pintype "output"))
      (node (ref "R10") (pin "2") (pinfunction "2_2") (pintype "passive"))
    )
    (net (code "51") (name "Net-(IC2B-OUT)") (class "Default")
      (node (ref "C13") (pin "2") (pinfunction "2_2") (pintype "passive"))
      (node (ref "IC2") (pin "7") (pinfunction "OUT_7") (pintype "output"))
      (node (ref "R10") (pin "1") (pinfunction "1_1") (pintype "passive"))
      (node (ref "R9") (pin "2") (pinfunction "2_2") (pintype "passive"))
    )
    (net (code "52") (name "Net-(IC3A--IN)") (class "Default")
      (node (ref "C8") (pin "1") (pinfunction "1_1") (pintype "passive"))
      (node (ref "IC3") (pin "2") (pinfunction "-IN_2") (pintype "input"))
      (node (ref "IC7") (pin "12") (pinfunction "OUT_12") (pintype "output"))
      (node (ref "R11") (pin "2") (pinfunction "2_2") (pintype "passive"))
    )
    (net (code "53") (name "Net-(IC3A-OUT)") (class "Default")
      (node (ref "C8") (pin "2") (pinfunction "2_2") (pintype "passive"))
      (node (ref "IC3") (pin "1") (pinfunction "OUT_1") (pintype "output"))
      (node (ref "IC7") (pin "11") (pinfunction "CTRL_11") (pintype "input"))
      (node (ref "IC9") (pin "14") (pinfunction "CTRL_14") (pintype "input"))
    )
    (net (code "54") (name "Net-(IC3B--IN)") (class "Default")
      (node (ref "IC3") (pin "6") (pinfunction "-IN_6") (pintype "input"))
      (node (ref "IC3") (pin "7") (pinfunction "OUT_7") (pintype "output"))
    )
    (net (code "55") (name "Net-(IC4A--IN)") (class "Default")
      (node (ref "C9") (pin "1") (pinfunction "1_1") (pintype "passive"))
      (node (ref "IC4") (pin "2") (pinfunction "-IN_2") (pintype "input"))
      (node (ref "R12") (pin "1") (pinfunction "1_1") (pintype "passive"))
      (node (ref "R16") (pin "2") (pinfunction "2_2") (pintype "passive"))
      (node (ref "R19") (pin "2") (pinfunction "2_2") (pintype "passive"))
    )
    (net (code "56") (name "Net-(IC4B--IN)") (class "Default")
      (node (ref "C10") (pin "1") (pinfunction "1_1") (pintype "passive"))
      (node (ref "IC4") (pin "6") (pinfunction "-IN_6") (pintype "input"))
      (node (ref "R13") (pin "1") (pinfunction "1_1") (pintype "passive"))
      (node (ref "R17") (pin "2") (pinfunction "2_2") (pintype "passive"))
      (node (ref "R20") (pin "2") (pinfunction "2_2") (pintype "passive"))
    )
    (net (code "57") (name "Net-(IC6A--IN)") (class "Default")
      (node (ref "C40") (pin "1") (pinfunction "1_1") (pintype "passive"))
      (node (ref "D6") (pin "A") (pinfunction "A_A") (pintype "passive"))
      (node (ref "IC6") (pin "2") (pinfunction "-IN_2") (pintype "input"))
      (node (ref "IC7") (pin "4") (pinfunction "OUT_4") (pintype "output"))
    )
    (net (code "58") (name "Net-(IC6B--IN)") (class "Default")
      (node (ref "C36") (pin "1") (pinfunction "1_1") (pintype "passive"))
      (node (ref "IC6") (pin "6") (pinfunction "-IN_6") (pintype "input"))
      (node (ref "IC7") (pin "13") (pinfunction "OUT_13") (pintype "output"))
    )
    (net (code "59") (name "Net-(IC7A-IN)") (class "Default")
      (node (ref "IC7") (pin "2") (pinfunction "IN_2") (pintype "input"))
      (node (ref "R40") (pin "2") (pinfunction "2_2") (pintype "passive"))
      (node (ref "R41") (pin "2") (pinfunction "2_2") (pintype "passive"))
    )
    (net (code "60") (name "Net-(IC7B-IN)") (class "Default")
      (node (ref "IC7") (pin "7") (pinfunction "IN_7") (pintype "input"))
      (node (ref "R42") (pin "2") (pinfunction "2_2") (pintype "passive"))
      (node (ref "R43") (pin "1") (pinfunction "1_1") (pintype "passive"))
    )
    (net (code "61") (name "Net-(IC7B-OUT)") (class "Default")
      (node (ref "IC7") (pin "5") (pinfunction "OUT_5") (pintype "output"))
      (node (ref "IC8") (pin "6") (pinfunction "-IN_6") (pintype "input"))
      (node (ref "R49") (pin "1") (pinfunction "1_1") (pintype "passive"))
    )
    (net (code "62") (name "Net-(IC7C-IN)") (class "Default")
      (node (ref "IC7") (pin "10") (pinfunction "IN_10") (pintype "input"))
      (node (ref "R24") (pin "2") (pinfunction "2_2") (pintype "passive"))
      (node (ref "R25") (pin "1") (pinfunction "1_1") (pintype "passive"))
    )
    (net (code "63") (name "Net-(IC7D-IN)") (class "Default")
      (node (ref "IC7") (pin "15") (pinfunction "IN_15") (pintype "input"))
      (node (ref "R23") (pin "2") (pinfunction "2_2") (pintype "passive"))
      (node (ref "R39") (pin "2") (pinfunction "2_2") (pintype "passive"))
    )
    (net (code "64") (name "Net-(IC7E-MODE)") (class "Default")
      (node (ref "IC7") (pin "1") (pinfunction "MODE_1") (pintype "input"))
      (node (ref "R37") (pin "2") (pinfunction "2_2") (pintype "passive"))
    )
    (net (code "65") (name "Net-(IC8A--IN)") (class "Default")
      (node (ref "IC8") (pin "2") (pinfunction "-IN_2") (pintype "input"))
      (node (ref "R44") (pin "1") (pinfunction "1_1") (pintype "passive"))
      (node (ref "R45") (pin "2") (pinfunction "2_2") (pintype "passive"))
      (node (ref "R46") (pin "1") (pinfunction "1_1") (pintype "passive"))
      (node (ref "R47") (pin "1") (pinfunction "1_1") (pintype "passive"))
      (node (ref "R48") (pin "2") (pinfunction "2_2") (pintype "passive"))
    )
    (net (code "66") (name "Net-(IC8B-OUT)") (class "Default")
      (node (ref "IC8") (pin "7") (pinfunction "OUT_7") (pintype "output"))
      (node (ref "R47") (pin "2") (pinfunction "2_2") (pintype "passive"))
      (node (ref "R49") (pin "2") (pinfunction "2_2") (pintype "passive"))
    )
    (net (code "67") (name "Net-(IC8C--IN)") (class "Default")
      (node (ref "IC8") (pin "9") (pinfunction "-IN_9") (pintype "input"))
      (node (ref "IC9") (pin "4") (pinfunction "OUT_4") (pintype "output"))
      (node (ref "R31") (pin "1") (pinfunction "1_1") (pintype "passive"))
    )
    (net (code "68") (name "Net-(IC8C-OUT)") (class "Default")
      (node (ref "IC8") (pin "8") (pinfunction "OUT_8") (pintype "output"))
      (node (ref "R29") (pin "1") (pinfunction "1_1") (pintype "passive"))
      (node (ref "R31") (pin "2") (pinfunction "2_2") (pintype "passive"))
    )
    (net (code "69") (name "Net-(IC8D--IN)") (class "Default")
      (node (ref "IC8") (pin "13") (pinfunction "-IN_13") (pintype "input"))
      (node (ref "R26") (pin "1") (pinfunction "1_1") (pintype "passive"))
      (node (ref "R27") (pin "1") (pinfunction "1_1") (pintype "passive"))
      (node (ref "R28") (pin "2") (pinfunction "2_2") (pintype "passive"))
      (node (ref "R29") (pin "2") (pinfunction "2_2") (pintype "passive"))
      (node (ref "R30") (pin "2") (pinfunction "2_2") (pintype "passive"))
    )
    (net (code "70") (name "Net-(IC9A-IN)") (class "Default")
      (node (ref "IC9") (pin "2") (pinfunction "IN_2") (pintype "input"))
      (node (ref "R50") (pin "1") (pinfunction "1_1") (pintype "passive"))
      (node (ref "R51") (pin "2") (pinfunction "2_2") (pintype "passive"))
    )
    (net (code "71") (name "Net-(IC9B-IN)") (class "Default")
      (node (ref "IC9") (pin "7") (pinfunction "IN_7") (pintype "input"))
      (node (ref "R52") (pin "2") (pinfunction "2_2") (pintype "passive"))
      (node (ref "R53") (pin "2") (pinfunction "2_2") (pintype "passive"))
    )
    (net (code "72") (name "Net-(IC9C-IN)") (class "Default")
      (node (ref "IC9") (pin "10") (pinfunction "IN_10") (pintype "input"))
      (node (ref "R35") (pin "2") (pinfunction "2_2") (pintype "passive"))
      (node (ref "R36") (pin "2") (pinfunction "2_2") (pintype "passive"))
    )
    (net (code "73") (name "Net-(IC9D-IN)") (class "Default")
      (node (ref "IC9") (pin "15") (pinfunction "IN_15") (pintype "input"))
      (node (ref "R32") (pin "2") (pinfunction "2_2") (pintype "passive"))
      (node (ref "R33") (pin "2") (pinfunction "2_2") (pintype "passive"))
      (node (ref "R34") (pin "2") (pinfunction "2_2") (pintype "passive"))
    )
    (net (code "74") (name "Net-(IC9E-MODE)") (class "Default")
      (node (ref "IC9") (pin "1") (pinfunction "MODE_1") (pintype "input"))
      (node (ref "R38") (pin "2") (pinfunction "2_2") (pintype "passive"))
    )
    (net (code "75") (name "Net-(IC10A--IN)") (class "Default")
      (node (ref "C41") (pin "1") (pinfunction "1_1") (pintype "passive"))
      (node (ref "IC10") (pin "2") (pinfunction "-IN_2") (pintype "input"))
      (node (ref "IC9") (pin "5") (pinfunction "OUT_5") (pintype "output"))
    )
    (net (code "76") (name "Net-(IC10B--IN)") (class "Default")
      (node (ref "C37") (pin "1") (pinfunction "1_1") (pintype "passive"))
      (node (ref "D4") (pin "A") (pinfunction "A_A") (pintype "passive"))
      (node (ref "IC10") (pin "6") (pinfunction "-IN_6") (pintype "input"))
      (node (ref "IC9") (pin "12") (pinfunction "OUT_12") (pintype "output"))
    )
    (net (code "77") (name "Net-(IC11A-RCK)") (class "Default")
      (node (ref "IC11") (pin "12") (pinfunction "RCK_12") (pintype "input"))
      (node (ref "J6") (pin "5") (pinfunction "5_5") (pintype "passive"))
    )
    (net (code "78") (name "Net-(IC11A-SCK)") (class "Default")
      (node (ref "IC11") (pin "11") (pinfunction "SCK_11") (pintype "input"))
      (node (ref "J6") (pin "4") (pinfunction "4_4") (pintype "passive"))
    )
    (net (code "79") (name "Net-(IC11A-SER)") (class "Default")
      (node (ref "IC11") (pin "14") (pinfunction "SER_14") (pintype "input"))
      (node (ref "J6") (pin "3") (pinfunction "3_3") (pintype "passive"))
    )
    (net (code "80") (name "Net-(IC12A-X)") (class "Default")
      (node (ref "IC12") (pin "14") (pinfunction "X_14") (pintype "bidirectional"))
      (node (ref "IC12") (pin "2") (pinfunction "Y0_2") (pintype "bidirectional"))
    )
    (net (code "81") (name "Net-(IC12A-Z)") (class "Default")
      (node (ref "IC12") (pin "4") (pinfunction "Z_4") (pintype "bidirectional"))
      (node (ref "R28") (pin "1") (pinfunction "1_1") (pintype "passive"))
    )
    (net (code "82") (name "Net-(IC13A-X)") (class "Default")
      (node (ref "IC13") (pin "14") (pinfunction "X_14") (pintype "bidirectional"))
      (node (ref "IC13") (pin "2") (pinfunction "Y0_2") (pintype "bidirectional"))
    )
    (net (code "83") (name "Net-(J1-PadT)") (class "Default")
      (node (ref "J1") (pin "T") (pinfunction "T_T") (pintype "passive"))
      (node (ref "R1") (pin "E") (pinfunction "E_E") (pintype "passive"))
    )
    (net (code "84") (name "Net-(J2-PadT)") (class "Default")
      (node (ref "J2") (pin "T") (pinfunction "T_T") (pintype "passive"))
      (node (ref "R2") (pin "S") (pinfunction "S_S") (pintype "passive"))
    )
    (net (code "85") (name "Net-(J3-Pad3)") (class "Default")
      (node (ref "J3") (pin "3") (pinfunction "3_3") (pintype "passive"))
      (node (ref "SW") (pin "1") (pinfunction "1_1") (pintype "passive"))
    )
    (net (code "86") (name "Net-(J4-Pad2)") (class "Default")
      (node (ref "J4") (pin "2") (pinfunction "2_2") (pintype "passive"))
      (node (ref "R15") (pin "1") (pinfunction "1_1") (pintype "passive"))
    )
    (net (code "87") (name "Net-(J4-Pad4)") (class "Default")
      (node (ref "J4") (pin "4") (pinfunction "4_4") (pintype "passive"))
      (node (ref "R22") (pin "1") (pinfunction "1_1") (pintype "passive"))
    )
    (net (code "88") (name "Net-(J4-Pad5)") (class "Default")
      (node (ref "J4") (pin "5") (pinfunction "5_5") (pintype "passive"))
      (node (ref "R8") (pin "1") (pinfunction "1_1") (pintype "passive"))
    )
    (net (code "89") (name "Net-(R4-A)") (class "Default")
      (node (ref "R16") (pin "1") (pinfunction "1_1") (pintype "passive"))
      (node (ref "R4") (pin "2") (pinfunction "S_2") (pintype "passive"))
      (node (ref "R4") (pin "3") (pinfunction "A_3") (pintype "passive"))
    )
    (net (code "90") (name "Net-(R5-A)") (class "Default")
      (node (ref "J4") (pin "3") (pinfunction "3_3") (pintype "passive"))
      (node (ref "R5") (pin "3") (pinfunction "A_3") (pintype "passive"))
    )
    (net (code "91") (name "Net-(R5-E)") (class "Default")
      (node (ref "R19") (pin "1") (pinfunction "1_1") (pintype "passive"))
      (node (ref "R5") (pin "1") (pinfunction "E_1") (pintype "passive"))
      (node (ref "R5") (pin "2") (pinfunction "S_2") (pintype "passive"))
    )
    (net (code "92") (name "Net-(R6-A)") (class "Default")
      (node (ref "J4") (pin "6") (pinfunction "6_6") (pintype "passive"))
      (node (ref "R6") (pin "3") (pinfunction "A_3") (pintype "passive"))
    )
    (net (code "93") (name "Net-(R6-E)") (class "Default")
      (node (ref "R20") (pin "1") (pinfunction "1_1") (pintype "passive"))
      (node (ref "R6") (pin "1") (pinfunction "E_1") (pintype "passive"))
      (node (ref "R6") (pin "2") (pinfunction "S_2") (pintype "passive"))
    )
    (net (code "94") (name "Net-(R7-A)") (class "Default")
      (node (ref "R17") (pin "1") (pinfunction "1_1") (pintype "passive"))
      (node (ref "R7") (pin "2") (pinfunction "S_2") (pintype "passive"))
      (node (ref "R7") (pin "3") (pinfunction "A_3") (pintype "passive"))
    )
    (net (code "95") (name "VCC") (class "Default")
      (node (ref "C20") (pin "1") (pinfunction "1_1") (pintype "passive"))
      (node (ref "C24") (pin "1") (pinfunction "1_1") (pintype "passive"))
      (node (ref "C29") (pin "1") (pinfunction "1_1") (pintype "passive"))
      (node (ref "C33") (pin "1") (pinfunction "1_1") (pintype "passive"))
      (node (ref "C35") (pin "1") (pinfunction "1_1") (pintype "passive"))
      (node (ref "C4") (pin "1") (pinfunction "1_1") (pintype "passive"))
      (node (ref "C45") (pin "1") (pinfunction "1_1") (pintype "passive"))
      (node (ref "C49") (pin "1") (pinfunction "1_1") (pintype "passive"))
      (node (ref "C5") (pin "1") (pinfunction "1_1") (pintype "passive"))
      (node (ref "C50") (pin "+") (pinfunction "+_+") (pintype "passive"))
      (node (ref "C51") (pin "1") (pinfunction "1_1") (pintype "passive"))
      (node (ref "C52") (pin "1") (pinfunction "1_1") (pintype "passive"))
      (node (ref "C53") (pin "1") (pinfunction "1_1") (pintype "passive"))
      (node (ref "IC10") (pin "8") (pinfunction "V+_8") (pintype "power_in"))
      (node (ref "IC11") (pin "10") (pinfunction "SCL_10") (pintype "input"))
      (node (ref "IC11") (pin "16") (pinfunction "VCC_16") (pintype "power_in"))
      (node (ref "IC12") (pin "16") (pinfunction "VCC_16") (pintype "power_in"))
      (node (ref "IC13") (pin "16") (pinfunction "VCC_16") (pintype "power_in"))
      (node (ref "IC14") (pin "OUT") (pinfunction "OUT_OUT") (pintype "passive"))
      (node (ref "IC2") (pin "8") (pinfunction "V+_8") (pintype "power_in"))
      (node (ref "IC3") (pin "8") (pinfunction "V+_8") (pintype "power_in"))
      (node (ref "IC4") (pin "8") (pinfunction "V+_8") (pintype "power_in"))
      (node (ref "IC6") (pin "8") (pinfunction "V+_8") (pintype "power_in"))
      (node (ref "IC7") (pin "16") (pinfunction "V+_16") (pintype "power_in"))
      (node (ref "IC8") (pin "4") (pinfunction "V+_4") (pintype "power_in"))
      (node (ref "IC9") (pin "16") (pinfunction "V+_16") (pintype "power_in"))
      (node (ref "J5") (pin "2") (pinfunction "2_2") (pintype "passive"))
      (node (ref "R37") (pin "1") (pinfunction "1_1") (pintype "passive"))
      (node (ref "R38") (pin "1") (pinfunction "1_1") (pintype "passive"))
    )
    (net (code "96") (name "VEE") (class "Default")
      (node (ref "C17") (pin "2") (pinfunction "2_2") (pintype "passive"))
      (node (ref "C18") (pin "2") (pinfunction "2_2") (pintype "passive"))
      (node (ref "C19") (pin "2") (pinfunction "2_2") (pintype "passive"))
      (node (ref "C27") (pin "2") (pinfunction "2_2") (pintype "passive"))
      (node (ref "C28") (pin "2") (pinfunction "2_2") (pintype "passive"))
      (node (ref "C32") (pin "2") (pinfunction "2_2") (pintype "passive"))
      (node (ref "C38") (pin "-") (pinfunction "-_-") (pintype "passive"))
      (node (ref "C39") (pin "2") (pinfunction "2_2") (pintype "passive"))
      (node (ref "C42") (pin "2") (pinfunction "2_2") (pintype "passive"))
      (node (ref "C48") (pin "2") (pinfunction "2_2") (pintype "passive"))
      (node (ref "C54") (pin "2") (pinfunction "2_2") (pintype "passive"))
      (node (ref "C55") (pin "2") (pinfunction "2_2") (pintype "passive"))
      (node (ref "IC10") (pin "4") (pinfunction "V-_4") (pintype "power_in"))
      (node (ref "IC12") (pin "7") (pinfunction "VEE_7") (pintype "power_in"))
      (node (ref "IC13") (pin "7") (pinfunction "VEE_7") (pintype "power_in"))
      (node (ref "IC2") (pin "4") (pinfunction "V-_4") (pintype "power_in"))
      (node (ref "IC3") (pin "4") (pinfunction "V-_4") (pintype "power_in"))
      (node (ref "IC4") (pin "4") (pinfunction "V-_4") (pintype "power_in"))
      (node (ref "IC5") (pin "OUT") (pinfunction "OUT_OUT") (pintype "passive"))
      (node (ref "IC6") (pin "4") (pinfunction "V-_4") (pintype "power_in"))
      (node (ref "IC7") (pin "9") (pinfunction "V-_9") (pintype "power_in"))
      (node (ref "IC8") (pin "11") (pinfunction "V-_11") (pintype "power_in"))
      (node (ref "IC9") (pin "9") (pinfunction "V-_9") (pintype "power_in"))
      (node (ref "R25") (pin "2") (pinfunction "2_2") (pintype "passive"))
      (node (ref "R4") (pin "1") (pinfunction "E_1") (pintype "passive"))
      (node (ref "R7") (pin "1") (pinfunction "E_1") (pintype "passive"))
    )
    (net (code "97") (name "unconnected-(IC1-Pad1)") (class "Default")
      (node (ref "IC1") (pin "1") (pinfunction "1_1") (pintype "passive"))
    )
    (net (code "98") (name "unconnected-(IC1-Pad6)") (class "Default")
      (node (ref "IC1") (pin "6") (pinfunction "6_6") (pintype "passive"))
    )
    (net (code "99") (name "unconnected-(IC11A-QG-Pad6)") (class "Default")
      (node (ref "IC11") (pin "6") (pinfunction "QG_6") (pintype "tri_state"))
    )
    (net (code "100") (name "unconnected-(IC11A-QH*-Pad9)") (class "Default")
      (node (ref "IC11") (pin "9") (pinfunction "QH*_9") (pintype "tri_state"))
    )
    (net (code "101") (name "unconnected-(IC11A-QH-Pad7)") (class "Default")
      (node (ref "IC11") (pin "7") (pinfunction "QH_7") (pintype "tri_state"))
    )
    (net (code "102") (name "unconnected-(J2-PadTN)") (class "Default")
      (node (ref "J2") (pin "TN") (pinfunction "TN_TN") (pintype "passive"))
    )
    (net (code "103") (name "unconnected-(J3-Pad2)") (class "Default")
      (node (ref "J3") (pin "2") (pinfunction "2_2") (pintype "passive"))
    )
    (net (code "104") (name "unconnected-(J6-Pad1)") (class "Default")
      (node (ref "J6") (pin "1") (pinfunction "1_1") (pintype "passive"))
    )
    (net (code "105") (name "unconnected-(J6-Pad6)") (class "Default")
      (node (ref "J6") (pin "6") (pinfunction "6_6") (pintype "passive"))
    )
  )
)
